# SparkFunVKeyVoltageKeypad2.net
KiCad netlist of a schematic drawn in EAGLE
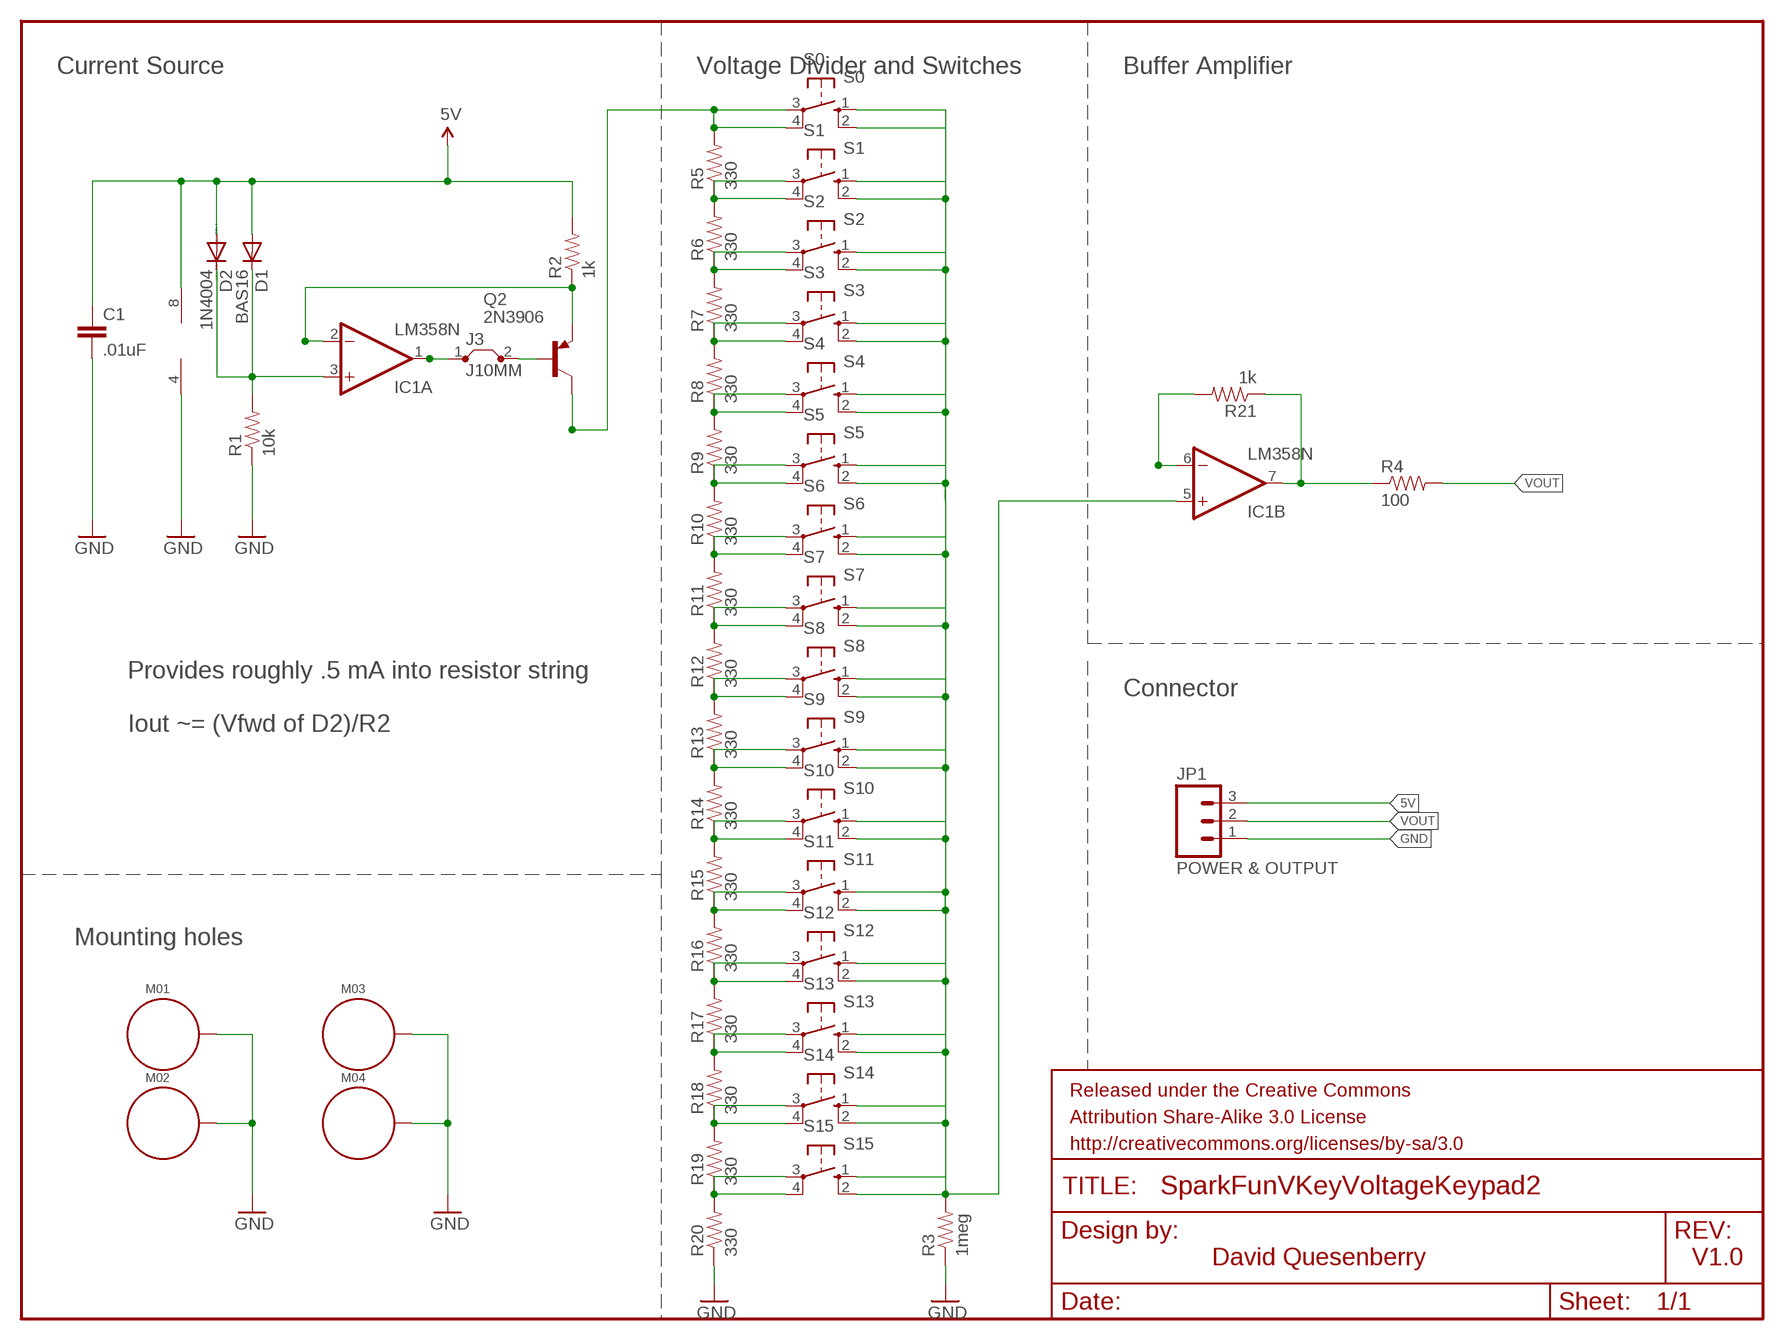
[diagram p0: schematic, sheet 1]

(export (version "E")
  (design (tool "Eeschema 10.0.6"))
  (components
    (comp (ref "C1")
      (value ".01uF")
      (footprint "eagle-import:0603-CAP")
      (libsource (lib "eagle-import") (part "10NF/10000PF-50V-10%(0603)"))
    )
    (comp (ref "D1")
      (value "BAS16")
      (footprint "eagle-import:SOD-323")
      (libsource (lib "eagle-import") (part "DIODESOD"))
    )
    (comp (ref "D2")
      (value "1N4004")
      (footprint "eagle-import:DO41-10")
      (libsource (lib "eagle-import") (part "1N4004"))
    )
    (comp (ref "FRAME1")
      (value "FRAME-LETTER")
      (footprint "eagle-import:CREATIVE_COMMONS")
      (libsource (lib "eagle-import") (part "FRAME-LETTER"))
    )
    (comp (ref "IC1")
      (value "LM358N")
      (footprint "eagle-import:DIL08")
      (libsource (lib "eagle-import") (part "LM358N"))
    )
    (comp (ref "J3")
      (value "J10MM")
      (footprint "eagle-import:10")
      (libsource (lib "eagle-import") (part "J10MM"))
    )
    (comp (ref "JP1")
      (value "POWER & OUTPUT")
      (footprint "eagle-import:1X03_NO_SILK")
      (libsource (lib "eagle-import") (part "M031X03_NO_SILK"))
    )
    (comp (ref "M01")
      (value "STANDOFF_ELECTRICAL")
      (footprint "eagle-import:STANDOFF-ELECTRICAL")
      (libsource (lib "eagle-import") (part "STANDOFF_ELECTRICAL"))
    )
    (comp (ref "M02")
      (value "STANDOFF_ELECTRICAL")
      (footprint "eagle-import:STANDOFF-ELECTRICAL")
      (libsource (lib "eagle-import") (part "STANDOFF_ELECTRICAL"))
    )
    (comp (ref "M03")
      (value "STANDOFF_ELECTRICAL")
      (footprint "eagle-import:STANDOFF-ELECTRICAL")
      (libsource (lib "eagle-import") (part "STANDOFF_ELECTRICAL"))
    )
    (comp (ref "M04")
      (value "STANDOFF_ELECTRICAL")
      (footprint "eagle-import:STANDOFF-ELECTRICAL")
      (libsource (lib "eagle-import") (part "STANDOFF_ELECTRICAL"))
    )
    (comp (ref "Q2")
      (value "2N3906")
      (footprint "eagle-import:TO92")
      (libsource (lib "eagle-import") (part "2N3906"))
    )
    (comp (ref "R1")
      (value "10k")
      (footprint "eagle-import:0603-RES")
      (libsource (lib "eagle-import") (part "10KOHM1/10W1%(0603)0603"))
    )
    (comp (ref "R2")
      (value "1k")
      (footprint "eagle-import:0603-RES")
      (libsource (lib "eagle-import") (part "1KOHM1/10W1%(0603)"))
    )
    (comp (ref "R3")
      (value "1meg")
      (footprint "eagle-import:0603-RES")
      (libsource (lib "eagle-import") (part "1M-1%"))
    )
    (comp (ref "R4")
      (value "100")
      (footprint "eagle-import:0603-RES")
      (libsource (lib "eagle-import") (part "100OHM1/10W1%(0603)"))
    )
    (comp (ref "R5")
      (value "330")
      (footprint "eagle-import:0603-RES")
      (libsource (lib "eagle-import") (part "330OHM1/10W1%(0603)"))
    )
    (comp (ref "R6")
      (value "330")
      (footprint "eagle-import:0603-RES")
      (fields (field (name "PROD_ID") "RES-00818"))
      (libsource (lib "eagle-import") (part "330OHM1/10W1%(0603)"))
    )
    (comp (ref "R7")
      (value "330")
      (footprint "eagle-import:0603-RES")
      (fields (field (name "PROD_ID") "RES-00818"))
      (libsource (lib "eagle-import") (part "330OHM1/10W1%(0603)"))
    )
    (comp (ref "R8")
      (value "330")
      (footprint "eagle-import:0603-RES")
      (fields (field (name "PROD_ID") "RES-00818"))
      (libsource (lib "eagle-import") (part "330OHM1/10W1%(0603)"))
    )
    (comp (ref "R9")
      (value "330")
      (footprint "eagle-import:0603-RES")
      (fields (field (name "PROD_ID") "RES-00818"))
      (libsource (lib "eagle-import") (part "330OHM1/10W1%(0603)"))
    )
    (comp (ref "R10")
      (value "330")
      (footprint "eagle-import:0603-RES")
      (fields (field (name "PROD_ID") "RES-00818"))
      (libsource (lib "eagle-import") (part "330OHM1/10W1%(0603)"))
    )
    (comp (ref "R11")
      (value "330")
      (footprint "eagle-import:0603-RES")
      (fields (field (name "PROD_ID") "RES-00818"))
      (libsource (lib "eagle-import") (part "330OHM1/10W1%(0603)"))
    )
    (comp (ref "R12")
      (value "330")
      (footprint "eagle-import:0603-RES")
      (fields (field (name "PROD_ID") "RES-00818"))
      (libsource (lib "eagle-import") (part "330OHM1/10W1%(0603)"))
    )
    (comp (ref "R13")
      (value "330")
      (footprint "eagle-import:0603-RES")
      (fields (field (name "PROD_ID") "RES-00818"))
      (libsource (lib "eagle-import") (part "330OHM1/10W1%(0603)"))
    )
    (comp (ref "R14")
      (value "330")
      (footprint "eagle-import:0603-RES")
      (fields (field (name "PROD_ID") "RES-00818"))
      (libsource (lib "eagle-import") (part "330OHM1/10W1%(0603)"))
    )
    (comp (ref "R15")
      (value "330")
      (footprint "eagle-import:0603-RES")
      (fields (field (name "PROD_ID") "RES-00818"))
      (libsource (lib "eagle-import") (part "330OHM1/10W1%(0603)"))
    )
    (comp (ref "R16")
      (value "330")
      (footprint "eagle-import:0603-RES")
      (libsource (lib "eagle-import") (part "330OHM1/10W1%(0603)"))
    )
    (comp (ref "R17")
      (value "330")
      (footprint "eagle-import:0603-RES")
      (libsource (lib "eagle-import") (part "330OHM1/10W1%(0603)"))
    )
    (comp (ref "R18")
      (value "330")
      (footprint "eagle-import:0603-RES")
      (libsource (lib "eagle-import") (part "330OHM1/10W1%(0603)"))
    )
    (comp (ref "R19")
      (value "330")
      (footprint "eagle-import:0603-RES")
      (libsource (lib "eagle-import") (part "330OHM1/10W1%(0603)"))
    )
    (comp (ref "R20")
      (value "330")
      (footprint "eagle-import:0603-RES")
      (fields (field (name "PROD_ID") "RES-00818"))
      (libsource (lib "eagle-import") (part "330OHM1/10W1%(0603)"))
    )
    (comp (ref "R21")
      (value "1k")
      (footprint "eagle-import:0603-RES")
      (libsource (lib "eagle-import") (part "1KOHM1/10W1%(0603)"))
    )
    (comp (ref "S0")
      (value "S0")
      (footprint "eagle-import:B3F-10XX")
      (fields (field (name "MPN") "B3F-1000"))
      (libsource (lib "eagle-import") (part "10-XX"))
    )
    (comp (ref "S1")
      (value "S1")
      (footprint "eagle-import:B3F-10XX")
      (fields (field (name "MPN") "B3F-1000"))
      (libsource (lib "eagle-import") (part "10-XX"))
    )
    (comp (ref "S2")
      (value "S2")
      (footprint "eagle-import:B3F-10XX")
      (fields (field (name "MPN") "B3F-1000"))
      (libsource (lib "eagle-import") (part "10-XX"))
    )
    (comp (ref "S3")
      (value "S3")
      (footprint "eagle-import:B3F-10XX")
      (fields (field (name "MPN") "B3F-1000"))
      (libsource (lib "eagle-import") (part "10-XX"))
    )
    (comp (ref "S4")
      (value "S4")
      (footprint "eagle-import:B3F-10XX")
      (fields (field (name "MPN") "B3F-1000"))
      (libsource (lib "eagle-import") (part "10-XX"))
    )
    (comp (ref "S5")
      (value "S5")
      (footprint "eagle-import:B3F-10XX")
      (fields (field (name "MPN") "B3F-1000"))
      (libsource (lib "eagle-import") (part "10-XX"))
    )
    (comp (ref "S6")
      (value "S6")
      (footprint "eagle-import:B3F-10XX")
      (fields (field (name "MPN") "B3F-1000"))
      (libsource (lib "eagle-import") (part "10-XX"))
    )
    (comp (ref "S7")
      (value "S7")
      (footprint "eagle-import:B3F-10XX")
      (fields (field (name "MPN") "B3F-1000"))
      (libsource (lib "eagle-import") (part "10-XX"))
    )
    (comp (ref "S8")
      (value "S8")
      (footprint "eagle-import:B3F-10XX")
      (fields (field (name "MPN") "B3F-1000"))
      (libsource (lib "eagle-import") (part "10-XX"))
    )
    (comp (ref "S9")
      (value "S9")
      (footprint "eagle-import:B3F-10XX")
      (fields (field (name "MPN") "B3F-1000"))
      (libsource (lib "eagle-import") (part "10-XX"))
    )
    (comp (ref "S10")
      (value "S10")
      (footprint "eagle-import:B3F-10XX")
      (fields (field (name "MPN") "B3F-1000"))
      (libsource (lib "eagle-import") (part "10-XX"))
    )
    (comp (ref "S11")
      (value "S11")
      (footprint "eagle-import:B3F-10XX")
      (fields (field (name "MPN") "B3F-1000"))
      (libsource (lib "eagle-import") (part "10-XX"))
    )
    (comp (ref "S12")
      (value "S12")
      (footprint "eagle-import:B3F-10XX")
      (fields (field (name "MPN") "B3F-1000"))
      (libsource (lib "eagle-import") (part "10-XX"))
    )
    (comp (ref "S13")
      (value "S13")
      (footprint "eagle-import:B3F-10XX")
      (fields (field (name "MPN") "B3F-1000"))
      (libsource (lib "eagle-import") (part "10-XX"))
    )
    (comp (ref "S14")
      (value "S14")
      (footprint "eagle-import:B3F-10XX")
      (fields (field (name "MPN") "B3F-1000"))
      (libsource (lib "eagle-import") (part "10-XX"))
    )
    (comp (ref "S15")
      (value "S15")
      (footprint "eagle-import:B3F-10XX")
      (fields (field (name "MPN") "B3F-1000"))
      (libsource (lib "eagle-import") (part "10-XX"))
    )
  )
  (nets
    (net (code "1") (name "5V") (class "Default")
      (node (ref "C1") (pin "1") (pinfunction "1_1") (pintype "passive"))
      (node (ref "D1") (pin "2") (pinfunction "A_2") (pintype "passive"))
      (node (ref "D2") (pin "A") (pinfunction "A_A") (pintype "passive"))
      (node (ref "IC1") (pin "8") (pinfunction "V+_8") (pintype "power_in"))
      (node (ref "JP1") (pin "3") (pinfunction "3_3") (pintype "passive"))
      (node (ref "R2") (pin "2") (pinfunction "2_2") (pintype "passive"))
    )
    (net (code "2") (name "GND") (class "Default")
      (node (ref "C1") (pin "2") (pinfunction "2_2") (pintype "passive"))
      (node (ref "IC1") (pin "4") (pinfunction "V-_4") (pintype "power_in"))
      (node (ref "JP1") (pin "1") (pinfunction "1_1") (pintype "passive"))
      (node (ref "M01") (pin "P1") (pinfunction "P$1_P1") (pintype "bidirectional"))
      (node (ref "M02") (pin "P1") (pinfunction "P$1_P1") (pintype "bidirectional"))
      (node (ref "M03") (pin "P1") (pinfunction "P$1_P1") (pintype "bidirectional"))
      (node (ref "M04") (pin "P1") (pinfunction "P$1_P1") (pintype "bidirectional"))
      (node (ref "R1") (pin "1") (pinfunction "1_1") (pintype "passive"))
      (node (ref "R20") (pin "1") (pinfunction "1_1") (pintype "passive"))
      (node (ref "R3") (pin "1") (pinfunction "1_1") (pintype "passive"))
    )
    (net (code "3") (name "Net-(D1-C)") (class "Default")
      (node (ref "D1") (pin "1") (pinfunction "C_1") (pintype "passive"))
      (node (ref "D2") (pin "C") (pinfunction "C_C") (pintype "passive"))
      (node (ref "IC1") (pin "3") (pinfunction "+IN_3") (pintype "input"))
      (node (ref "R1") (pin "2") (pinfunction "2_2") (pintype "passive"))
    )
    (net (code "4") (name "Net-(IC1A--IN)") (class "Default")
      (node (ref "IC1") (pin "2") (pinfunction "-IN_2") (pintype "input"))
      (node (ref "Q2") (pin "3") (pinfunction "E_3") (pintype "passive"))
      (node (ref "R2") (pin "1") (pinfunction "1_1") (pintype "passive"))
    )
    (net (code "5") (name "Net-(IC1A-OUT)") (class "Default")
      (node (ref "IC1") (pin "1") (pinfunction "OUT_1") (pintype "output"))
      (node (ref "J3") (pin "1") (pinfunction "1_1") (pintype "passive"))
    )
    (net (code "6") (name "Net-(IC1B-+IN)") (class "Default")
      (node (ref "IC1") (pin "5") (pinfunction "+IN_5") (pintype "input"))
      (node (ref "R3") (pin "2") (pinfunction "2_2") (pintype "passive"))
      (node (ref "S0") (pin "1") (pinfunction "S_1") (pintype "passive"))
      (node (ref "S0") (pin "2") (pinfunction "S1_2") (pintype "passive"))
      (node (ref "S1") (pin "1") (pinfunction "S_1") (pintype "passive"))
      (node (ref "S1") (pin "2") (pinfunction "S1_2") (pintype "passive"))
      (node (ref "S10") (pin "1") (pinfunction "S_1") (pintype "passive"))
      (node (ref "S10") (pin "2") (pinfunction "S1_2") (pintype "passive"))
      (node (ref "S11") (pin "1") (pinfunction "S_1") (pintype "passive"))
      (node (ref "S11") (pin "2") (pinfunction "S1_2") (pintype "passive"))
      (node (ref "S12") (pin "1") (pinfunction "S_1") (pintype "passive"))
      (node (ref "S12") (pin "2") (pinfunction "S1_2") (pintype "passive"))
      (node (ref "S13") (pin "1") (pinfunction "S_1") (pintype "passive"))
      (node (ref "S13") (pin "2") (pinfunction "S1_2") (pintype "passive"))
      (node (ref "S14") (pin "1") (pinfunction "S_1") (pintype "passive"))
      (node (ref "S14") (pin "2") (pinfunction "S1_2") (pintype "passive"))
      (node (ref "S15") (pin "1") (pinfunction "S_1") (pintype "passive"))
      (node (ref "S15") (pin "2") (pinfunction "S1_2") (pintype "passive"))
      (node (ref "S2") (pin "1") (pinfunction "S_1") (pintype "passive"))
      (node (ref "S2") (pin "2") (pinfunction "S1_2") (pintype "passive"))
      (node (ref "S3") (pin "1") (pinfunction "S_1") (pintype "passive"))
      (node (ref "S3") (pin "2") (pinfunction "S1_2") (pintype "passive"))
      (node (ref "S4") (pin "1") (pinfunction "S_1") (pintype "passive"))
      (node (ref "S4") (pin "2") (pinfunction "S1_2") (pintype "passive"))
      (node (ref "S5") (pin "1") (pinfunction "S_1") (pintype "passive"))
      (node (ref "S5") (pin "2") (pinfunction "S1_2") (pintype "passive"))
      (node (ref "S6") (pin "1") (pinfunction "S_1") (pintype "passive"))
      (node (ref "S6") (pin "2") (pinfunction "S1_2") (pintype "passive"))
      (node (ref "S7") (pin "1") (pinfunction "S_1") (pintype "passive"))
      (node (ref "S7") (pin "2") (pinfunction "S1_2") (pintype "passive"))
      (node (ref "S8") (pin "1") (pinfunction "S_1") (pintype "passive"))
      (node (ref "S8") (pin "2") (pinfunction "S1_2") (pintype "passive"))
      (node (ref "S9") (pin "1") (pinfunction "S_1") (pintype "passive"))
      (node (ref "S9") (pin "2") (pinfunction "S1_2") (pintype "passive"))
    )
    (net (code "7") (name "Net-(IC1B--IN)") (class "Default")
      (node (ref "IC1") (pin "6") (pinfunction "-IN_6") (pintype "input"))
      (node (ref "R21") (pin "2") (pinfunction "2_2") (pintype "passive"))
    )
    (net (code "8") (name "Net-(IC1B-OUT)") (class "Default")
      (node (ref "IC1") (pin "7") (pinfunction "OUT_7") (pintype "output"))
      (node (ref "R21") (pin "1") (pinfunction "1_1") (pintype "passive"))
      (node (ref "R4") (pin "1") (pinfunction "1_1") (pintype "passive"))
    )
    (net (code "9") (name "Net-(Q2-B)") (class "Default")
      (node (ref "J3") (pin "2") (pinfunction "2_2") (pintype "passive"))
      (node (ref "Q2") (pin "2") (pinfunction "B_2") (pintype "passive"))
    )
    (net (code "10") (name "Net-(Q2-C)") (class "Default")
      (node (ref "Q2") (pin "1") (pinfunction "C_1") (pintype "passive"))
      (node (ref "R5") (pin "2") (pinfunction "2_2") (pintype "passive"))
      (node (ref "S0") (pin "3") (pinfunction "P_3") (pintype "passive"))
      (node (ref "S0") (pin "4") (pinfunction "P1_4") (pintype "passive"))
    )
    (net (code "11") (name "Net-(S1-P)") (class "Default")
      (node (ref "R5") (pin "1") (pinfunction "1_1") (pintype "passive"))
      (node (ref "R6") (pin "2") (pinfunction "2_2") (pintype "passive"))
      (node (ref "S1") (pin "3") (pinfunction "P_3") (pintype "passive"))
      (node (ref "S1") (pin "4") (pinfunction "P1_4") (pintype "passive"))
    )
    (net (code "12") (name "Net-(S2-P)") (class "Default")
      (node (ref "R6") (pin "1") (pinfunction "1_1") (pintype "passive"))
      (node (ref "R7") (pin "2") (pinfunction "2_2") (pintype "passive"))
      (node (ref "S2") (pin "3") (pinfunction "P_3") (pintype "passive"))
      (node (ref "S2") (pin "4") (pinfunction "P1_4") (pintype "passive"))
    )
    (net (code "13") (name "Net-(S3-P)") (class "Default")
      (node (ref "R7") (pin "1") (pinfunction "1_1") (pintype "passive"))
      (node (ref "R8") (pin "2") (pinfunction "2_2") (pintype "passive"))
      (node (ref "S3") (pin "3") (pinfunction "P_3") (pintype "passive"))
      (node (ref "S3") (pin "4") (pinfunction "P1_4") (pintype "passive"))
    )
    (net (code "14") (name "Net-(S4-P)") (class "Default")
      (node (ref "R8") (pin "1") (pinfunction "1_1") (pintype "passive"))
      (node (ref "R9") (pin "2") (pinfunction "2_2") (pintype "passive"))
      (node (ref "S4") (pin "3") (pinfunction "P_3") (pintype "passive"))
      (node (ref "S4") (pin "4") (pinfunction "P1_4") (pintype "passive"))
    )
    (net (code "15") (name "Net-(S5-P)") (class "Default")
      (node (ref "R10") (pin "2") (pinfunction "2_2") (pintype "passive"))
      (node (ref "R9") (pin "1") (pinfunction "1_1") (pintype "passive"))
      (node (ref "S5") (pin "3") (pinfunction "P_3") (pintype "passive"))
      (node (ref "S5") (pin "4") (pinfunction "P1_4") (pintype "passive"))
    )
    (net (code "16") (name "Net-(S6-P)") (class "Default")
      (node (ref "R10") (pin "1") (pinfunction "1_1") (pintype "passive"))
      (node (ref "R11") (pin "2") (pinfunction "2_2") (pintype "passive"))
      (node (ref "S6") (pin "3") (pinfunction "P_3") (pintype "passive"))
      (node (ref "S6") (pin "4") (pinfunction "P1_4") (pintype "passive"))
    )
    (net (code "17") (name "Net-(S7-P)") (class "Default")
      (node (ref "R11") (pin "1") (pinfunction "1_1") (pintype "passive"))
      (node (ref "R12") (pin "2") (pinfunction "2_2") (pintype "passive"))
      (node (ref "S7") (pin "3") (pinfunction "P_3") (pintype "passive"))
      (node (ref "S7") (pin "4") (pinfunction "P1_4") (pintype "passive"))
    )
    (net (code "18") (name "Net-(S8-P)") (class "Default")
      (node (ref "R12") (pin "1") (pinfunction "1_1") (pintype "passive"))
      (node (ref "R13") (pin "2") (pinfunction "2_2") (pintype "passive"))
      (node (ref "S8") (pin "3") (pinfunction "P_3") (pintype "passive"))
      (node (ref "S8") (pin "4") (pinfunction "P1_4") (pintype "passive"))
    )
    (net (code "19") (name "Net-(S9-P)") (class "Default")
      (node (ref "R13") (pin "1") (pinfunction "1_1") (pintype "passive"))
      (node (ref "R14") (pin "2") (pinfunction "2_2") (pintype "passive"))
      (node (ref "S9") (pin "3") (pinfunction "P_3") (pintype "passive"))
      (node (ref "S9") (pin "4") (pinfunction "P1_4") (pintype "passive"))
    )
    (net (code "20") (name "Net-(S10-P)") (class "Default")
      (node (ref "R14") (pin "1") (pinfunction "1_1") (pintype "passive"))
      (node (ref "R15") (pin "2") (pinfunction "2_2") (pintype "passive"))
      (node (ref "S10") (pin "3") (pinfunction "P_3") (pintype "passive"))
      (node (ref "S10") (pin "4") (pinfunction "P1_4") (pintype "passive"))
    )
    (net (code "21") (name "Net-(S11-P)") (class "Default")
      (node (ref "R15") (pin "1") (pinfunction "1_1") (pintype "passive"))
      (node (ref "R16") (pin "2") (pinfunction "2_2") (pintype "passive"))
      (node (ref "S11") (pin "3") (pinfunction "P_3") (pintype "passive"))
      (node (ref "S11") (pin "4") (pinfunction "P1_4") (pintype "passive"))
    )
    (net (code "22") (name "Net-(S12-P)") (class "Default")
      (node (ref "R16") (pin "1") (pinfunction "1_1") (pintype "passive"))
      (node (ref "R17") (pin "2") (pinfunction "2_2") (pintype "passive"))
      (node (ref "S12") (pin "3") (pinfunction "P_3") (pintype "passive"))
      (node (ref "S12") (pin "4") (pinfunction "P1_4") (pintype "passive"))
    )
    (net (code "23") (name "Net-(S13-P)") (class "Default")
      (node (ref "R17") (pin "1") (pinfunction "1_1") (pintype "passive"))
      (node (ref "R18") (pin "2") (pinfunction "2_2") (pintype "passive"))
      (node (ref "S13") (pin "3") (pinfunction "P_3") (pintype "passive"))
      (node (ref "S13") (pin "4") (pinfunction "P1_4") (pintype "passive"))
    )
    (net (code "24") (name "Net-(S14-P)") (class "Default")
      (node (ref "R18") (pin "1") (pinfunction "1_1") (pintype "passive"))
      (node (ref "R19") (pin "2") (pinfunction "2_2") (pintype "passive"))
      (node (ref "S14") (pin "3") (pinfunction "P_3") (pintype "passive"))
      (node (ref "S14") (pin "4") (pinfunction "P1_4") (pintype "passive"))
    )
    (net (code "25") (name "Net-(S15-P)") (class "Default")
      (node (ref "R19") (pin "1") (pinfunction "1_1") (pintype "passive"))
      (node (ref "R20") (pin "2") (pinfunction "2_2") (pintype "passive"))
      (node (ref "S15") (pin "3") (pinfunction "P_3") (pintype "passive"))
      (node (ref "S15") (pin "4") (pinfunction "P1_4") (pintype "passive"))
    )
    (net (code "26") (name "VOUT") (class "Default")
      (node (ref "JP1") (pin "2") (pinfunction "2_2") (pintype "passive"))
      (node (ref "R4") (pin "2") (pinfunction "2_2") (pintype "passive"))
    )
  )
)
